# SMARC_Pinout-1.net
KiCad netlist of a schematic drawn in Altium Designer
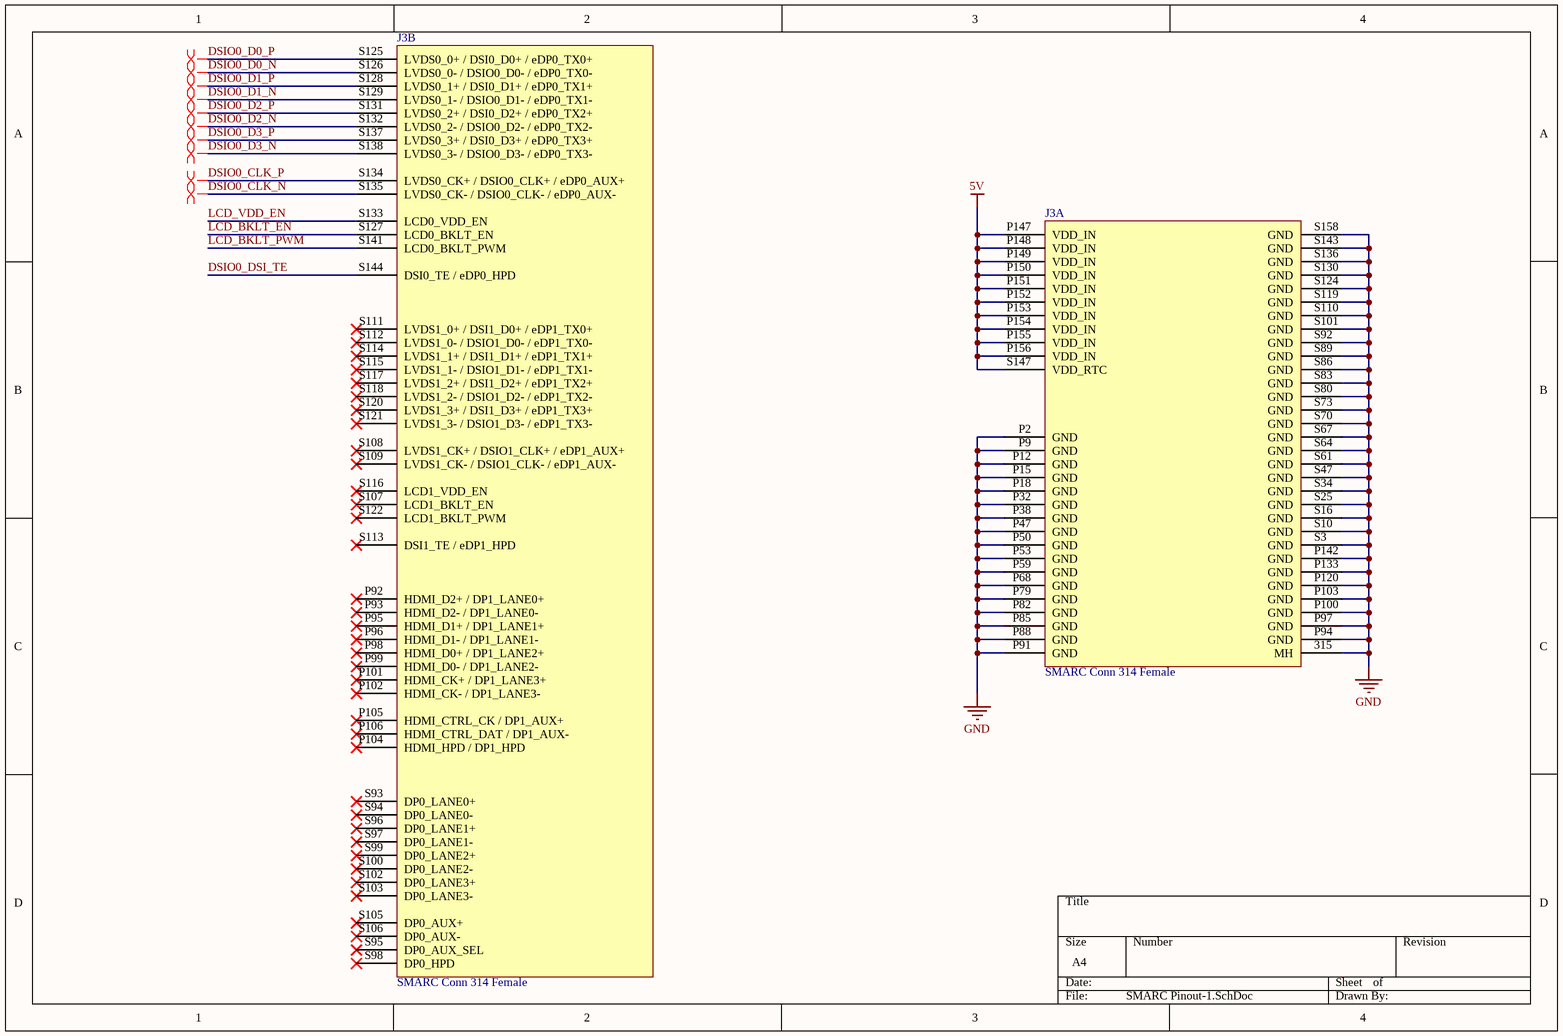
[diagram p0: SMARC Pinout-1.SchDoc]

(export (version "E")
  (design (tool "Eeschema 10.0.6"))
  (components
    (comp (ref "J3")
      (value "SMARC Conn 314 Female")
      (footprint "SMARC 314 Female")
      (libsource (lib "Master") (part "SMARC Conn 314 Female"))
    )
  )
  (nets
    (net (code "1") (name "/DSIO0_CLK_N") (class "Default")
      (node (ref "J3") (pin "S135") (pinfunction "LVDS0_CK-_/_DSIO0_CLK-_/_eDP0_AUX-_S135") (pintype "passive"))
    )
    (net (code "2") (name "/DSIO0_CLK_P") (class "Default")
      (node (ref "J3") (pin "S134") (pinfunction "LVDS0_CK+_/_DSIO0_CLK+_/_eDP0_AUX+_S134") (pintype "passive"))
    )
    (net (code "3") (name "/DSIO0_D0_N") (class "Default")
      (node (ref "J3") (pin "S126") (pinfunction "LVDS0_0-_/_DSIO0_D0-_/_eDP0_TX0-_S126") (pintype "passive"))
    )
    (net (code "4") (name "/DSIO0_D0_P") (class "Default")
      (node (ref "J3") (pin "S125") (pinfunction "LVDS0_0+_/_DSI0_D0+_/_eDP0_TX0+_S125") (pintype "passive"))
    )
    (net (code "5") (name "/DSIO0_D1_N") (class "Default")
      (node (ref "J3") (pin "S129") (pinfunction "LVDS0_1-_/_DSIO0_D1-_/_eDP0_TX1-_S129") (pintype "passive"))
    )
    (net (code "6") (name "/DSIO0_D1_P") (class "Default")
      (node (ref "J3") (pin "S128") (pinfunction "LVDS0_1+_/_DSI0_D1+_/_eDP0_TX1+_S128") (pintype "passive"))
    )
    (net (code "7") (name "/DSIO0_D2_N") (class "Default")
      (node (ref "J3") (pin "S132") (pinfunction "LVDS0_2-_/_DSIO0_D2-_/_eDP0_TX2-_S132") (pintype "passive"))
    )
    (net (code "8") (name "/DSIO0_D2_P") (class "Default")
      (node (ref "J3") (pin "S131") (pinfunction "LVDS0_2+_/_DSI0_D2+_/_eDP0_TX2+_S131") (pintype "passive"))
    )
    (net (code "9") (name "/DSIO0_D3_N") (class "Default")
      (node (ref "J3") (pin "S138") (pinfunction "LVDS0_3-_/_DSIO0_D3-_/_eDP0_TX3-_S138") (pintype "passive"))
    )
    (net (code "10") (name "/DSIO0_D3_P") (class "Default")
      (node (ref "J3") (pin "S137") (pinfunction "LVDS0_3+_/_DSI0_D3+_/_eDP0_TX3+_S137") (pintype "passive"))
    )
    (net (code "11") (name "/DSIO0_DSI_TE") (class "Default")
      (node (ref "J3") (pin "S144") (pinfunction "DSI0_TE_/_eDP0_HPD_S144") (pintype "passive"))
    )
    (net (code "12") (name "/LCD_BKLT_EN") (class "Default")
      (node (ref "J3") (pin "S127") (pinfunction "LCD0_BKLT_EN_S127") (pintype "passive"))
    )
    (net (code "13") (name "/LCD_BKLT_PWM") (class "Default")
      (node (ref "J3") (pin "S141") (pinfunction "LCD0_BKLT_PWM_S141") (pintype "passive"))
    )
    (net (code "14") (name "/LCD_VDD_EN") (class "Default")
      (node (ref "J3") (pin "S133") (pinfunction "LCD0_VDD_EN_S133") (pintype "passive"))
    )
    (net (code "15") (name "5V") (class "Default")
      (node (ref "J3") (pin "P147") (pinfunction "VDD_IN_P147") (pintype "passive"))
      (node (ref "J3") (pin "P148") (pinfunction "VDD_IN_P148") (pintype "passive"))
      (node (ref "J3") (pin "P149") (pinfunction "VDD_IN_P149") (pintype "passive"))
      (node (ref "J3") (pin "P150") (pinfunction "VDD_IN_P150") (pintype "passive"))
      (node (ref "J3") (pin "P151") (pinfunction "VDD_IN_P151") (pintype "passive"))
      (node (ref "J3") (pin "P152") (pinfunction "VDD_IN_P152") (pintype "passive"))
      (node (ref "J3") (pin "P153") (pinfunction "VDD_IN_P153") (pintype "passive"))
      (node (ref "J3") (pin "P154") (pinfunction "VDD_IN_P154") (pintype "passive"))
      (node (ref "J3") (pin "P155") (pinfunction "VDD_IN_P155") (pintype "passive"))
      (node (ref "J3") (pin "P156") (pinfunction "VDD_IN_P156") (pintype "passive"))
      (node (ref "J3") (pin "S147") (pinfunction "VDD_RTC_S147") (pintype "passive"))
    )
    (net (code "16") (name "GND") (class "Default")
      (node (ref "J3") (pin "315") (pinfunction "MH_315") (pintype "passive"))
      (node (ref "J3") (pin "P100") (pinfunction "GND_P100") (pintype "passive"))
      (node (ref "J3") (pin "P103") (pinfunction "GND_P103") (pintype "passive"))
      (node (ref "J3") (pin "P12") (pinfunction "GND_P12") (pintype "passive"))
      (node (ref "J3") (pin "P120") (pinfunction "GND_P120") (pintype "passive"))
      (node (ref "J3") (pin "P133") (pinfunction "GND_P133") (pintype "passive"))
      (node (ref "J3") (pin "P142") (pinfunction "GND_P142") (pintype "passive"))
      (node (ref "J3") (pin "P15") (pinfunction "GND_P15") (pintype "passive"))
      (node (ref "J3") (pin "P18") (pinfunction "GND_P18") (pintype "passive"))
      (node (ref "J3") (pin "P2") (pinfunction "GND_P2") (pintype "passive"))
      (node (ref "J3") (pin "P32") (pinfunction "GND_P32") (pintype "passive"))
      (node (ref "J3") (pin "P38") (pinfunction "GND_P38") (pintype "passive"))
      (node (ref "J3") (pin "P47") (pinfunction "GND_P47") (pintype "passive"))
      (node (ref "J3") (pin "P50") (pinfunction "GND_P50") (pintype "passive"))
      (node (ref "J3") (pin "P53") (pinfunction "GND_P53") (pintype "passive"))
      (node (ref "J3") (pin "P59") (pinfunction "GND_P59") (pintype "passive"))
      (node (ref "J3") (pin "P68") (pinfunction "GND_P68") (pintype "passive"))
      (node (ref "J3") (pin "P79") (pinfunction "GND_P79") (pintype "passive"))
      (node (ref "J3") (pin "P82") (pinfunction "GND_P82") (pintype "passive"))
      (node (ref "J3") (pin "P85") (pinfunction "GND_P85") (pintype "passive"))
      (node (ref "J3") (pin "P88") (pinfunction "GND_P88") (pintype "passive"))
      (node (ref "J3") (pin "P9") (pinfunction "GND_P9") (pintype "passive"))
      (node (ref "J3") (pin "P91") (pinfunction "GND_P91") (pintype "passive"))
      (node (ref "J3") (pin "P94") (pinfunction "GND_P94") (pintype "passive"))
      (node (ref "J3") (pin "P97") (pinfunction "GND_P97") (pintype "passive"))
      (node (ref "J3") (pin "S10") (pinfunction "GND_S10") (pintype "passive"))
      (node (ref "J3") (pin "S101") (pinfunction "GND_S101") (pintype "passive"))
      (node (ref "J3") (pin "S110") (pinfunction "GND_S110") (pintype "passive"))
      (node (ref "J3") (pin "S119") (pinfunction "GND_S119") (pintype "passive"))
      (node (ref "J3") (pin "S124") (pinfunction "GND_S124") (pintype "passive"))
      (node (ref "J3") (pin "S130") (pinfunction "GND_S130") (pintype "passive"))
      (node (ref "J3") (pin "S136") (pinfunction "GND_S136") (pintype "passive"))
      (node (ref "J3") (pin "S143") (pinfunction "GND_S143") (pintype "passive"))
      (node (ref "J3") (pin "S158") (pinfunction "GND_S158") (pintype "passive"))
      (node (ref "J3") (pin "S16") (pinfunction "GND_S16") (pintype "passive"))
      (node (ref "J3") (pin "S25") (pinfunction "GND_S25") (pintype "passive"))
      (node (ref "J3") (pin "S3") (pinfunction "GND_S3") (pintype "passive"))
      (node (ref "J3") (pin "S34") (pinfunction "GND_S34") (pintype "passive"))
      (node (ref "J3") (pin "S47") (pinfunction "GND_S47") (pintype "passive"))
      (node (ref "J3") (pin "S61") (pinfunction "GND_S61") (pintype "passive"))
      (node (ref "J3") (pin "S64") (pinfunction "GND_S64") (pintype "passive"))
      (node (ref "J3") (pin "S67") (pinfunction "GND_S67") (pintype "passive"))
      (node (ref "J3") (pin "S70") (pinfunction "GND_S70") (pintype "passive"))
      (node (ref "J3") (pin "S73") (pinfunction "GND_S73") (pintype "passive"))
      (node (ref "J3") (pin "S80") (pinfunction "GND_S80") (pintype "passive"))
      (node (ref "J3") (pin "S83") (pinfunction "GND_S83") (pintype "passive"))
      (node (ref "J3") (pin "S86") (pinfunction "GND_S86") (pintype "passive"))
      (node (ref "J3") (pin "S89") (pinfunction "GND_S89") (pintype "passive"))
      (node (ref "J3") (pin "S92") (pinfunction "GND_S92") (pintype "passive"))
    )
    (net (code "17") (name "unconnected-(J3B-DP0_AUX+-PadS105)") (class "Default")
      (node (ref "J3") (pin "S105") (pinfunction "DP0_AUX+_S105") (pintype "passive+no_connect"))
    )
    (net (code "18") (name "unconnected-(J3B-DP0_AUX--PadS106)") (class "Default")
      (node (ref "J3") (pin "S106") (pinfunction "DP0_AUX-_S106") (pintype "passive+no_connect"))
    )
    (net (code "19") (name "unconnected-(J3B-DP0_AUX_SEL-PadS95)") (class "Default")
      (node (ref "J3") (pin "S95") (pinfunction "DP0_AUX_SEL_S95") (pintype "passive+no_connect"))
    )
    (net (code "20") (name "unconnected-(J3B-DP0_HPD-PadS98)") (class "Default")
      (node (ref "J3") (pin "S98") (pinfunction "DP0_HPD_S98") (pintype "passive+no_connect"))
    )
    (net (code "21") (name "unconnected-(J3B-DP0_LANE0+-PadS93)") (class "Default")
      (node (ref "J3") (pin "S93") (pinfunction "DP0_LANE0+_S93") (pintype "passive+no_connect"))
    )
    (net (code "22") (name "unconnected-(J3B-DP0_LANE0--PadS94)") (class "Default")
      (node (ref "J3") (pin "S94") (pinfunction "DP0_LANE0-_S94") (pintype "passive+no_connect"))
    )
    (net (code "23") (name "unconnected-(J3B-DP0_LANE1+-PadS96)") (class "Default")
      (node (ref "J3") (pin "S96") (pinfunction "DP0_LANE1+_S96") (pintype "passive+no_connect"))
    )
    (net (code "24") (name "unconnected-(J3B-DP0_LANE1--PadS97)") (class "Default")
      (node (ref "J3") (pin "S97") (pinfunction "DP0_LANE1-_S97") (pintype "passive+no_connect"))
    )
    (net (code "25") (name "unconnected-(J3B-DP0_LANE2+-PadS99)") (class "Default")
      (node (ref "J3") (pin "S99") (pinfunction "DP0_LANE2+_S99") (pintype "passive+no_connect"))
    )
    (net (code "26") (name "unconnected-(J3B-DP0_LANE2--PadS100)") (class "Default")
      (node (ref "J3") (pin "S100") (pinfunction "DP0_LANE2-_S100") (pintype "passive+no_connect"))
    )
    (net (code "27") (name "unconnected-(J3B-DP0_LANE3+-PadS102)") (class "Default")
      (node (ref "J3") (pin "S102") (pinfunction "DP0_LANE3+_S102") (pintype "passive+no_connect"))
    )
    (net (code "28") (name "unconnected-(J3B-DP0_LANE3--PadS103)") (class "Default")
      (node (ref "J3") (pin "S103") (pinfunction "DP0_LANE3-_S103") (pintype "passive+no_connect"))
    )
    (net (code "29") (name "unconnected-(J3B-DSI1_TE_{slash}_eDP1_HPD-PadS113)") (class "Default")
      (node (ref "J3") (pin "S113") (pinfunction "DSI1_TE_/_eDP1_HPD_S113") (pintype "passive+no_connect"))
    )
    (net (code "30") (name "unconnected-(J3B-HDMI_CK+_{slash}_DP1_LANE3+-PadP101)") (class "Default")
      (node (ref "J3") (pin "P101") (pinfunction "HDMI_CK+_/_DP1_LANE3+_P101") (pintype "passive+no_connect"))
    )
    (net (code "31") (name "unconnected-(J3B-HDMI_CK-_{slash}_DP1_LANE3--PadP102)") (class "Default")
      (node (ref "J3") (pin "P102") (pinfunction "HDMI_CK-_/_DP1_LANE3-_P102") (pintype "passive+no_connect"))
    )
    (net (code "32") (name "unconnected-(J3B-HDMI_CTRL_CK_{slash}_DP1_AUX+-PadP105)") (class "Default")
      (node (ref "J3") (pin "P105") (pinfunction "HDMI_CTRL_CK_/_DP1_AUX+_P105") (pintype "passive+no_connect"))
    )
    (net (code "33") (name "unconnected-(J3B-HDMI_CTRL_DAT_{slash}_DP1_AUX--PadP106)") (class "Default")
      (node (ref "J3") (pin "P106") (pinfunction "HDMI_CTRL_DAT_/_DP1_AUX-_P106") (pintype "passive+no_connect"))
    )
    (net (code "34") (name "unconnected-(J3B-HDMI_D0+_{slash}_DP1_LANE2+-PadP98)") (class "Default")
      (node (ref "J3") (pin "P98") (pinfunction "HDMI_D0+_/_DP1_LANE2+_P98") (pintype "passive+no_connect"))
    )
    (net (code "35") (name "unconnected-(J3B-HDMI_D0-_{slash}_DP1_LANE2--PadP99)") (class "Default")
      (node (ref "J3") (pin "P99") (pinfunction "HDMI_D0-_/_DP1_LANE2-_P99") (pintype "passive+no_connect"))
    )
    (net (code "36") (name "unconnected-(J3B-HDMI_D1+_{slash}_DP1_LANE1+-PadP95)") (class "Default")
      (node (ref "J3") (pin "P95") (pinfunction "HDMI_D1+_/_DP1_LANE1+_P95") (pintype "passive+no_connect"))
    )
    (net (code "37") (name "unconnected-(J3B-HDMI_D1-_{slash}_DP1_LANE1--PadP96)") (class "Default")
      (node (ref "J3") (pin "P96") (pinfunction "HDMI_D1-_/_DP1_LANE1-_P96") (pintype "passive+no_connect"))
    )
    (net (code "38") (name "unconnected-(J3B-HDMI_D2+_{slash}_DP1_LANE0+-PadP92)") (class "Default")
      (node (ref "J3") (pin "P92") (pinfunction "HDMI_D2+_/_DP1_LANE0+_P92") (pintype "passive+no_connect"))
    )
    (net (code "39") (name "unconnected-(J3B-HDMI_D2-_{slash}_DP1_LANE0--PadP93)") (class "Default")
      (node (ref "J3") (pin "P93") (pinfunction "HDMI_D2-_/_DP1_LANE0-_P93") (pintype "passive+no_connect"))
    )
    (net (code "40") (name "unconnected-(J3B-HDMI_HPD_{slash}_DP1_HPD-PadP104)") (class "Default")
      (node (ref "J3") (pin "P104") (pinfunction "HDMI_HPD_/_DP1_HPD_P104") (pintype "passive+no_connect"))
    )
    (net (code "41") (name "unconnected-(J3B-LCD1_BKLT_EN-PadS107)") (class "Default")
      (node (ref "J3") (pin "S107") (pinfunction "LCD1_BKLT_EN_S107") (pintype "passive+no_connect"))
    )
    (net (code "42") (name "unconnected-(J3B-LCD1_BKLT_PWM-PadS122)") (class "Default")
      (node (ref "J3") (pin "S122") (pinfunction "LCD1_BKLT_PWM_S122") (pintype "passive+no_connect"))
    )
    (net (code "43") (name "unconnected-(J3B-LCD1_VDD_EN-PadS116)") (class "Default")
      (node (ref "J3") (pin "S116") (pinfunction "LCD1_VDD_EN_S116") (pintype "passive+no_connect"))
    )
    (net (code "44") (name "unconnected-(J3B-LVDS1_0+_{slash}_DSI1_D0+_{slash}_eDP1_TX0+-PadS111)") (class "Default")
      (node (ref "J3") (pin "S111") (pinfunction "LVDS1_0+_/_DSI1_D0+_/_eDP1_TX0+_S111") (pintype "passive+no_connect"))
    )
    (net (code "45") (name "unconnected-(J3B-LVDS1_0-_{slash}_DSIO1_D0-_{slash}_eDP1_TX0--PadS112)") (class "Default")
      (node (ref "J3") (pin "S112") (pinfunction "LVDS1_0-_/_DSIO1_D0-_/_eDP1_TX0-_S112") (pintype "passive+no_connect"))
    )
    (net (code "46") (name "unconnected-(J3B-LVDS1_1+_{slash}_DSI1_D1+_{slash}_eDP1_TX1+-PadS114)") (class "Default")
      (node (ref "J3") (pin "S114") (pinfunction "LVDS1_1+_/_DSI1_D1+_/_eDP1_TX1+_S114") (pintype "passive+no_connect"))
    )
    (net (code "47") (name "unconnected-(J3B-LVDS1_1-_{slash}_DSIO1_D1-_{slash}_eDP1_TX1--PadS115)") (class "Default")
      (node (ref "J3") (pin "S115") (pinfunction "LVDS1_1-_/_DSIO1_D1-_/_eDP1_TX1-_S115") (pintype "passive+no_connect"))
    )
    (net (code "48") (name "unconnected-(J3B-LVDS1_2+_{slash}_DSI1_D2+_{slash}_eDP1_TX2+-PadS117)") (class "Default")
      (node (ref "J3") (pin "S117") (pinfunction "LVDS1_2+_/_DSI1_D2+_/_eDP1_TX2+_S117") (pintype "passive+no_connect"))
    )
    (net (code "49") (name "unconnected-(J3B-LVDS1_2-_{slash}_DSIO1_D2-_{slash}_eDP1_TX2--PadS118)") (class "Default")
      (node (ref "J3") (pin "S118") (pinfunction "LVDS1_2-_/_DSIO1_D2-_/_eDP1_TX2-_S118") (pintype "passive+no_connect"))
    )
    (net (code "50") (name "unconnected-(J3B-LVDS1_3+_{slash}_DSI1_D3+_{slash}_eDP1_TX3+-PadS120)") (class "Default")
      (node (ref "J3") (pin "S120") (pinfunction "LVDS1_3+_/_DSI1_D3+_/_eDP1_TX3+_S120") (pintype "passive+no_connect"))
    )
    (net (code "51") (name "unconnected-(J3B-LVDS1_3-_{slash}_DSIO1_D3-_{slash}_eDP1_TX3--PadS121)") (class "Default")
      (node (ref "J3") (pin "S121") (pinfunction "LVDS1_3-_/_DSIO1_D3-_/_eDP1_TX3-_S121") (pintype "passive+no_connect"))
    )
    (net (code "52") (name "unconnected-(J3B-LVDS1_CK+_{slash}_DSIO1_CLK+_{slash}_eDP1_AUX+-PadS108)") (class "Default")
      (node (ref "J3") (pin "S108") (pinfunction "LVDS1_CK+_/_DSIO1_CLK+_/_eDP1_AUX+_S108") (pintype "passive+no_connect"))
    )
    (net (code "53") (name "unconnected-(J3B-LVDS1_CK-_{slash}_DSIO1_CLK-_{slash}_eDP1_AUX--PadS109)") (class "Default")
      (node (ref "J3") (pin "S109") (pinfunction "LVDS1_CK-_/_DSIO1_CLK-_/_eDP1_AUX-_S109") (pintype "passive+no_connect"))
    )
  )
)
